# MCLK_Oscillator.net
KiCad netlist of a schematic drawn in Altium Designer
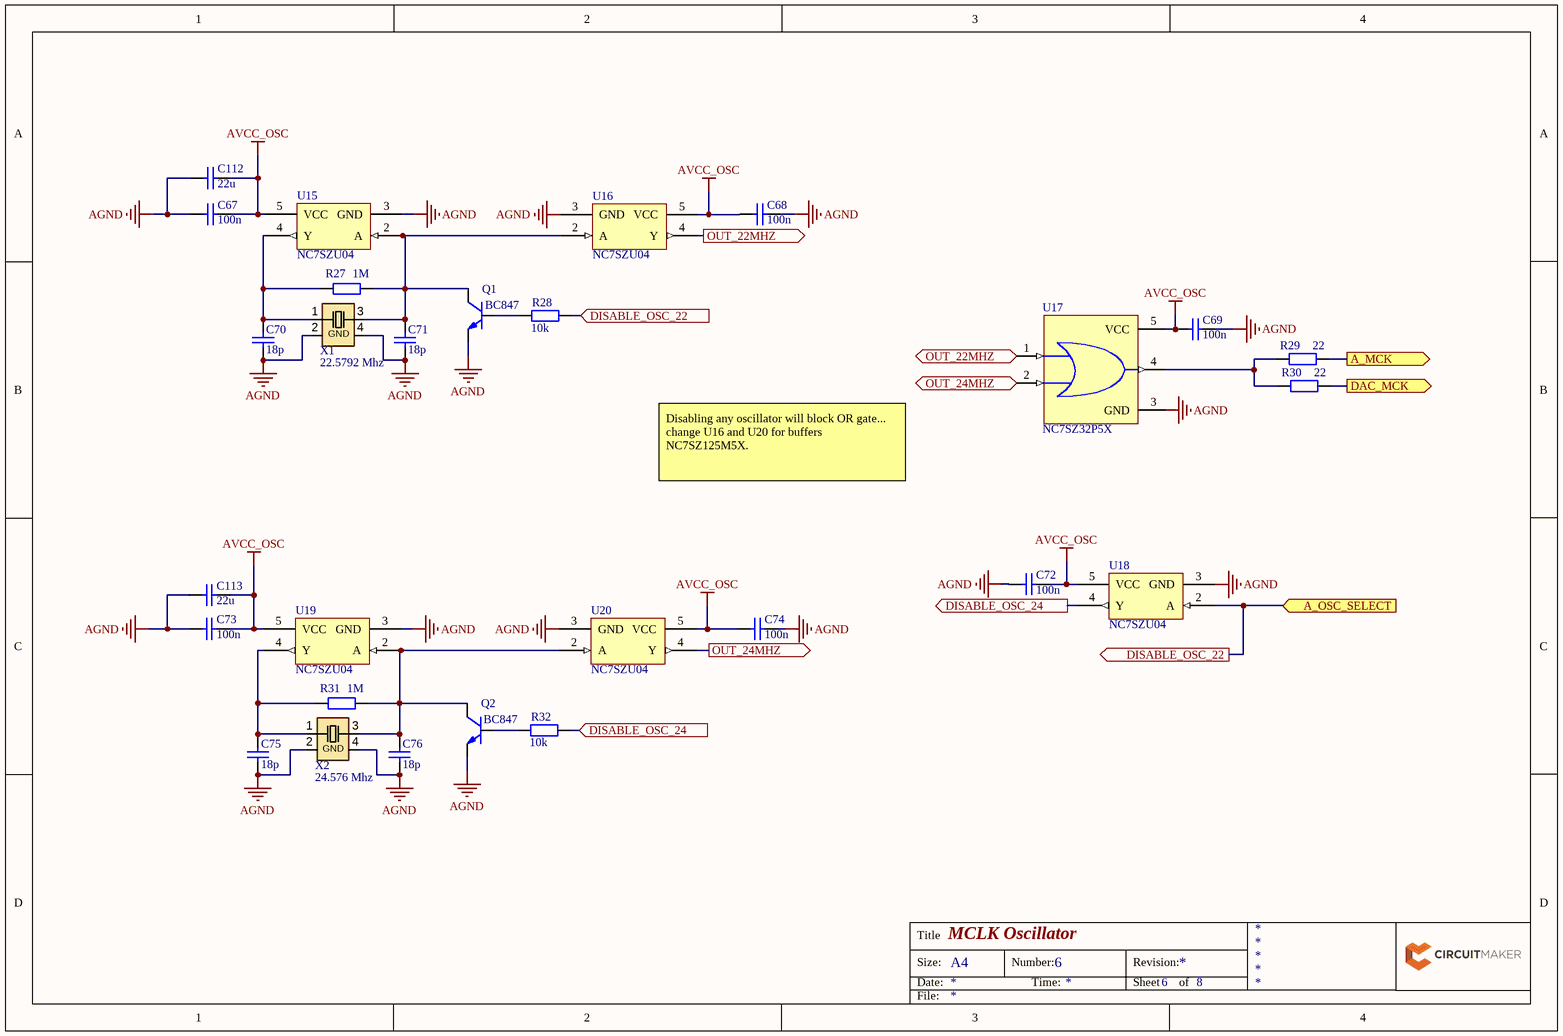
[diagram p0: MCLK_Oscillator.SchDoc]

(export (version "E")
  (design (tool "Eeschema 10.0.6"))
  (components
    (comp (ref "C67")
      (value "100n")
      (footprint "PCB-rf0pzaa82dpbeu9l4sxm-1")
      (description "Generic Capacitor 0603")
      (fields (field (name "LCSC PART #") "C14663") (field (name "LCSC PART #_1") "C109474"))
      (libsource (lib "FavoritesLibrary") (part "SYM-x8hddryxw4o380xfi98v-1"))
    )
    (comp (ref "C68")
      (value "100n")
      (footprint "PCB-rf0pzaa82dpbeu9l4sxm-1")
      (description "Generic Capacitor 0603")
      (fields (field (name "LCSC PART #") "C14663") (field (name "LCSC PART #_1") "C109474"))
      (libsource (lib "FavoritesLibrary") (part "SYM-x8hddryxw4o380xfi98v-1"))
    )
    (comp (ref "C69")
      (value "100n")
      (footprint "PCB-rf0pzaa82dpbeu9l4sxm-1")
      (description "Generic Capacitor 0603")
      (fields (field (name "LCSC PART #") "C14663") (field (name "LCSC PART #_1") "C109474"))
      (libsource (lib "FavoritesLibrary") (part "SYM-x8hddryxw4o380xfi98v-1"))
    )
    (comp (ref "C70")
      (value "18p")
      (footprint "PCB-rf0pzaa82dpbeu9l4sxm-1")
      (description "Generic Capacitor 0603")
      (fields (field (name "LCSC PART #") "C1679"))
      (libsource (lib "FavoritesLibrary") (part "SYM-x8hddryxw4o380xfi98v-1"))
    )
    (comp (ref "C71")
      (value "18p")
      (footprint "PCB-rf0pzaa82dpbeu9l4sxm-1")
      (description "Generic Capacitor 0603")
      (fields (field (name "LCSC PART #") "C1679"))
      (libsource (lib "FavoritesLibrary") (part "SYM-x8hddryxw4o380xfi98v-1"))
    )
    (comp (ref "C72")
      (value "100n")
      (footprint "PCB-rf0pzaa82dpbeu9l4sxm-1")
      (description "Generic Capacitor 0603")
      (fields (field (name "LCSC PART #") "C14663") (field (name "LCSC PART #_1") "C109474"))
      (libsource (lib "FavoritesLibrary") (part "SYM-x8hddryxw4o380xfi98v-1"))
    )
    (comp (ref "C73")
      (value "100n")
      (footprint "PCB-rf0pzaa82dpbeu9l4sxm-1")
      (description "Generic Capacitor 0603")
      (fields (field (name "LCSC PART #") "C14663") (field (name "LCSC PART #_1") "C109474"))
      (libsource (lib "FavoritesLibrary") (part "SYM-x8hddryxw4o380xfi98v-1"))
    )
    (comp (ref "C74")
      (value "100n")
      (footprint "PCB-rf0pzaa82dpbeu9l4sxm-1")
      (description "Generic Capacitor 0603")
      (fields (field (name "LCSC PART #") "C14663") (field (name "LCSC PART #_1") "C109474"))
      (libsource (lib "FavoritesLibrary") (part "SYM-x8hddryxw4o380xfi98v-1"))
    )
    (comp (ref "C75")
      (value "18p")
      (footprint "PCB-rf0pzaa82dpbeu9l4sxm-1")
      (description "Generic Capacitor 0603")
      (fields (field (name "LCSC PART #") "C1679"))
      (libsource (lib "FavoritesLibrary") (part "SYM-x8hddryxw4o380xfi98v-1"))
    )
    (comp (ref "C76")
      (value "18p")
      (footprint "PCB-rf0pzaa82dpbeu9l4sxm-1")
      (description "Generic Capacitor 0603")
      (fields (field (name "LCSC PART #") "C1679"))
      (libsource (lib "FavoritesLibrary") (part "SYM-x8hddryxw4o380xfi98v-1"))
    )
    (comp (ref "C112")
      (value "22u")
      (footprint "PCB-rf0pzaa82dpbeu9l4sxm-1")
      (description "Generic Capacitor 0603")
      (fields (field (name "LCSC PART #") "C59461"))
      (libsource (lib "FavoritesLibrary") (part "SYM-x8hddryxw4o380xfi98v-1"))
    )
    (comp (ref "C113")
      (value "22u")
      (footprint "PCB-rf0pzaa82dpbeu9l4sxm-1")
      (description "Generic Capacitor 0603")
      (fields (field (name "LCSC PART #") "C59461"))
      (libsource (lib "FavoritesLibrary") (part "SYM-x8hddryxw4o380xfi98v-1"))
    )
    (comp (ref "Q1")
      (value "BC847")
      (footprint "SOT23-BEC")
      (description "TRANS NPN 45V 0.1A SOT23")
      (fields (field (name "MANUFACTURER PART NUMBER") "BC847B,215"))
      (libsource (lib "CommunityVault") (part "NXP-NPN-3"))
    )
    (comp (ref "Q2")
      (value "BC847")
      (footprint "SOT23-BEC")
      (description "TRANS NPN 45V 0.1A SOT23")
      (fields (field (name "MANUFACTURER PART NUMBER") "BC847B,215"))
      (libsource (lib "CommunityVault") (part "NXP-NPN-3"))
    )
    (comp (ref "R27")
      (value "1M")
      (footprint "PCB-3d5y3t7f8drf35yjcj59-1")
      (description "Resistor 0603")
      (fields (field (name "LCSC PART #") "C22935"))
      (libsource (lib "FavoritesLibrary") (part "SYM-xcu3s4ikiffkkgbeyow5-1"))
    )
    (comp (ref "R28")
      (value "10k")
      (footprint "PCB-3d5y3t7f8drf35yjcj59-1")
      (description "Resistor 0603")
      (fields (field (name "LCSC PART #") "C25804"))
      (libsource (lib "FavoritesLibrary") (part "SYM-xcu3s4ikiffkkgbeyow5-1"))
    )
    (comp (ref "R29")
      (value "22")
      (footprint "PCB-3d5y3t7f8drf35yjcj59-1")
      (description "Resistor 0603")
      (fields (field (name "LCSC PART #") "C23345"))
      (libsource (lib "") (part "SYM-xcu3s4ikiffkkgbeyow5-1_1"))
    )
    (comp (ref "R30")
      (value "22")
      (footprint "PCB-3d5y3t7f8drf35yjcj59-1")
      (description "Resistor 0603")
      (fields (field (name "LCSC PART #") "C23345"))
      (libsource (lib "") (part "SYM-xcu3s4ikiffkkgbeyow5-1_1"))
    )
    (comp (ref "R31")
      (value "1M")
      (footprint "PCB-3d5y3t7f8drf35yjcj59-1")
      (description "Resistor 0603")
      (fields (field (name "LCSC PART #") "C22935"))
      (libsource (lib "FavoritesLibrary") (part "SYM-xcu3s4ikiffkkgbeyow5-1"))
    )
    (comp (ref "R32")
      (value "10k")
      (footprint "PCB-3d5y3t7f8drf35yjcj59-1")
      (description "Resistor 0603")
      (fields (field (name "LCSC PART #") "C25804"))
      (libsource (lib "FavoritesLibrary") (part "SYM-xcu3s4ikiffkkgbeyow5-1"))
    )
    (comp (ref "U15")
      (value "NC7SZU04")
      (footprint "PCB-wxeqetr75037g92pbgyq-1")
      (description "NC7SZU04 Series 5.5 V SMT Tinny Logic UHS Unbuffered Inverter - SOT-23-5")
      (fields (field (name "MANUFACTURER PART NUMBER") "NC7SZU04M5X"))
      (libsource (lib "FavoritesLibrary") (part "SYM-4ef282fea2d39135-1"))
    )
    (comp (ref "U16")
      (value "NC7SZU04")
      (footprint "PCB-wxeqetr75037g92pbgyq-1")
      (description "NC7SZU04 Series 5.5 V SMT Tinny Logic UHS Unbuffered Inverter - SOT-23-5")
      (fields (field (name "MANUFACTURER PART NUMBER") "NC7SZU04M5X"))
      (libsource (lib "") (part "SYM-4ef282fea2d39135-1_1"))
    )
    (comp (ref "U17")
      (value "NC7SZ32P5X")
      (footprint "PCB-eypsu81inaog57bsahf2-1")
      (description "NC7SZ32 Series 5.5 V Surface Mount TinyLogic®UHS 2-Input OR Gate - SC-70-5")
      (libsource (lib "CommunityVault") (part "SYM-7e2eb72341d3a1e9-1"))
    )
    (comp (ref "U18")
      (value "NC7SZU04")
      (footprint "PCB-wxeqetr75037g92pbgyq-1")
      (description "NC7SZU04 Series 5.5 V SMT Tinny Logic UHS Unbuffered Inverter - SOT-23-5")
      (fields (field (name "MANUFACTURER PART NUMBER") "NC7SZU04M5X"))
      (libsource (lib "FavoritesLibrary") (part "SYM-4ef282fea2d39135-1"))
    )
    (comp (ref "U19")
      (value "NC7SZU04")
      (footprint "PCB-wxeqetr75037g92pbgyq-1")
      (description "NC7SZU04 Series 5.5 V SMT Tinny Logic UHS Unbuffered Inverter - SOT-23-5")
      (fields (field (name "MANUFACTURER PART NUMBER") "NC7SZU04M5X"))
      (libsource (lib "FavoritesLibrary") (part "SYM-4ef282fea2d39135-1"))
    )
    (comp (ref "U20")
      (value "NC7SZU04")
      (footprint "PCB-wxeqetr75037g92pbgyq-1")
      (description "NC7SZU04 Series 5.5 V SMT Tinny Logic UHS Unbuffered Inverter - SOT-23-5")
      (fields (field (name "MANUFACTURER PART NUMBER") "NC7SZU04M5X"))
      (libsource (lib "") (part "SYM-4ef282fea2d39135-1_1"))
    )
    (comp (ref "X1")
      (value "22.5792 Mhz")
      (footprint "PCB-5cl8jn5un4pdqd8b4poj-1")
      (description "Crystal 18.432MHz ±20ppm (Tol) ±30ppm (Stability) 18pF FUND 80Ohm 4-Pin Mini-CSMD T/R")
      (libsource (lib "CommunityVault") (part "SYM-a7446b0f29ac7883-1"))
    )
    (comp (ref "X2")
      (value "24.576 Mhz")
      (footprint "PCB-5cl8jn5un4pdqd8b4poj-1")
      (description "Crystal 18.432MHz ±20ppm (Tol) ±30ppm (Stability) 18pF FUND 80Ohm 4-Pin Mini-CSMD T/R")
      (libsource (lib "CommunityVault") (part "SYM-a7446b0f29ac7883-1"))
    )
  )
  (nets
    (net (code "1") (name "/A_MCK") (class "Default")
      (node (ref "R29") (pin "1") (pinfunction "1_1") (pintype "passive"))
    )
    (net (code "2") (name "/A_OSC_SELECT") (class "Default")
      (node (ref "R28") (pin "2") (pinfunction "2_2") (pintype "passive"))
      (node (ref "U18") (pin "2") (pinfunction "A_2") (pintype "input"))
    )
    (net (code "3") (name "/DAC_MCK") (class "Default")
      (node (ref "R30") (pin "1") (pinfunction "1_1") (pintype "passive"))
    )
    (net (code "4") (name "/DISABLE_OSC_24") (class "Default")
      (node (ref "R32") (pin "2") (pinfunction "2_2") (pintype "passive"))
      (node (ref "U18") (pin "4") (pinfunction "Y_4") (pintype "output"))
    )
    (net (code "5") (name "/OUT_22MHZ") (class "Default")
      (node (ref "U16") (pin "4") (pinfunction "Y_4") (pintype "output"))
      (node (ref "U17") (pin "1") (pinfunction "A_1") (pintype "input"))
    )
    (net (code "6") (name "/OUT_24MHZ") (class "Default")
      (node (ref "U17") (pin "2") (pinfunction "B_2") (pintype "input"))
      (node (ref "U20") (pin "4") (pinfunction "Y_4") (pintype "output"))
    )
    (net (code "7") (name "AGND") (class "Default")
      (node (ref "C112") (pin "2") (pinfunction "2_2") (pintype "passive"))
      (node (ref "C113") (pin "2") (pinfunction "2_2") (pintype "passive"))
      (node (ref "C67") (pin "2") (pinfunction "2_2") (pintype "passive"))
      (node (ref "C68") (pin "1") (pinfunction "1_1") (pintype "passive"))
      (node (ref "C69") (pin "1") (pinfunction "1_1") (pintype "passive"))
      (node (ref "C70") (pin "2") (pinfunction "2_2") (pintype "passive"))
      (node (ref "C71") (pin "2") (pinfunction "2_2") (pintype "passive"))
      (node (ref "C72") (pin "2") (pinfunction "2_2") (pintype "passive"))
      (node (ref "C73") (pin "2") (pinfunction "2_2") (pintype "passive"))
      (node (ref "C74") (pin "1") (pinfunction "1_1") (pintype "passive"))
      (node (ref "C75") (pin "2") (pinfunction "2_2") (pintype "passive"))
      (node (ref "C76") (pin "2") (pinfunction "2_2") (pintype "passive"))
      (node (ref "Q1") (pin "E") (pinfunction "E_E") (pintype "passive"))
      (node (ref "Q2") (pin "E") (pinfunction "E_E") (pintype "passive"))
      (node (ref "U15") (pin "3") (pinfunction "GND_3") (pintype "power_in"))
      (node (ref "U16") (pin "3") (pinfunction "GND_3") (pintype "power_in"))
      (node (ref "U17") (pin "3") (pinfunction "GND_3") (pintype "passive"))
      (node (ref "U18") (pin "3") (pinfunction "GND_3") (pintype "power_in"))
      (node (ref "U19") (pin "3") (pinfunction "GND_3") (pintype "power_in"))
      (node (ref "U20") (pin "3") (pinfunction "GND_3") (pintype "power_in"))
      (node (ref "X1") (pin "2") (pinfunction "gnd_2") (pintype "passive"))
      (node (ref "X1") (pin "4") (pinfunction "gnd_4") (pintype "passive"))
      (node (ref "X2") (pin "2") (pinfunction "gnd_2") (pintype "passive"))
      (node (ref "X2") (pin "4") (pinfunction "gnd_4") (pintype "passive"))
    )
    (net (code "8") (name "AVCC_OSC") (class "Default")
      (node (ref "C112") (pin "1") (pinfunction "1_1") (pintype "passive"))
      (node (ref "C113") (pin "1") (pinfunction "1_1") (pintype "passive"))
      (node (ref "C67") (pin "1") (pinfunction "1_1") (pintype "passive"))
      (node (ref "C68") (pin "2") (pinfunction "2_2") (pintype "passive"))
      (node (ref "C69") (pin "2") (pinfunction "2_2") (pintype "passive"))
      (node (ref "C72") (pin "1") (pinfunction "1_1") (pintype "passive"))
      (node (ref "C73") (pin "1") (pinfunction "1_1") (pintype "passive"))
      (node (ref "C74") (pin "2") (pinfunction "2_2") (pintype "passive"))
      (node (ref "U15") (pin "5") (pinfunction "VCC_5") (pintype "power_in"))
      (node (ref "U16") (pin "5") (pinfunction "VCC_5") (pintype "power_in"))
      (node (ref "U17") (pin "5") (pinfunction "VCC_5") (pintype "passive"))
      (node (ref "U18") (pin "5") (pinfunction "VCC_5") (pintype "power_in"))
      (node (ref "U19") (pin "5") (pinfunction "VCC_5") (pintype "power_in"))
      (node (ref "U20") (pin "5") (pinfunction "VCC_5") (pintype "power_in"))
    )
    (net (code "9") (name "Net-(Q1-PadB)") (class "Default")
      (node (ref "Q1") (pin "B") (pinfunction "B_B") (pintype "passive"))
      (node (ref "R28") (pin "1") (pinfunction "1_1") (pintype "passive"))
    )
    (net (code "10") (name "Net-(Q2-PadB)") (class "Default")
      (node (ref "Q2") (pin "B") (pinfunction "B_B") (pintype "passive"))
      (node (ref "R32") (pin "1") (pinfunction "1_1") (pintype "passive"))
    )
    (net (code "11") (name "Net-(U15-A)") (class "Default")
      (node (ref "C71") (pin "1") (pinfunction "1_1") (pintype "passive"))
      (node (ref "Q1") (pin "C") (pinfunction "C_C") (pintype "passive"))
      (node (ref "R27") (pin "2") (pinfunction "2_2") (pintype "passive"))
      (node (ref "U15") (pin "2") (pinfunction "A_2") (pintype "input"))
      (node (ref "U16") (pin "2") (pinfunction "A_2") (pintype "input"))
      (node (ref "X1") (pin "3") (pinfunction "3_3") (pintype "passive"))
    )
    (net (code "12") (name "Net-(U15-Y)") (class "Default")
      (node (ref "C70") (pin "1") (pinfunction "1_1") (pintype "passive"))
      (node (ref "R27") (pin "1") (pinfunction "1_1") (pintype "passive"))
      (node (ref "U15") (pin "4") (pinfunction "Y_4") (pintype "output"))
      (node (ref "X1") (pin "1") (pinfunction "1_1") (pintype "passive"))
    )
    (net (code "13") (name "Net-(U17-Y)") (class "Default")
      (node (ref "R29") (pin "2") (pinfunction "2_2") (pintype "passive"))
      (node (ref "R30") (pin "2") (pinfunction "2_2") (pintype "passive"))
      (node (ref "U17") (pin "4") (pinfunction "Y_4") (pintype "output"))
    )
    (net (code "14") (name "Net-(U19-A)") (class "Default")
      (node (ref "C76") (pin "1") (pinfunction "1_1") (pintype "passive"))
      (node (ref "Q2") (pin "C") (pinfunction "C_C") (pintype "passive"))
      (node (ref "R31") (pin "2") (pinfunction "2_2") (pintype "passive"))
      (node (ref "U19") (pin "2") (pinfunction "A_2") (pintype "input"))
      (node (ref "U20") (pin "2") (pinfunction "A_2") (pintype "input"))
      (node (ref "X2") (pin "3") (pinfunction "3_3") (pintype "passive"))
    )
    (net (code "15") (name "Net-(U19-Y)") (class "Default")
      (node (ref "C75") (pin "1") (pinfunction "1_1") (pintype "passive"))
      (node (ref "R31") (pin "1") (pinfunction "1_1") (pintype "passive"))
      (node (ref "U19") (pin "4") (pinfunction "Y_4") (pintype "output"))
      (node (ref "X2") (pin "1") (pinfunction "1_1") (pintype "passive"))
    )
  )
)
